# LCD_big.net
KiCad netlist of a schematic drawn in Altium Designer
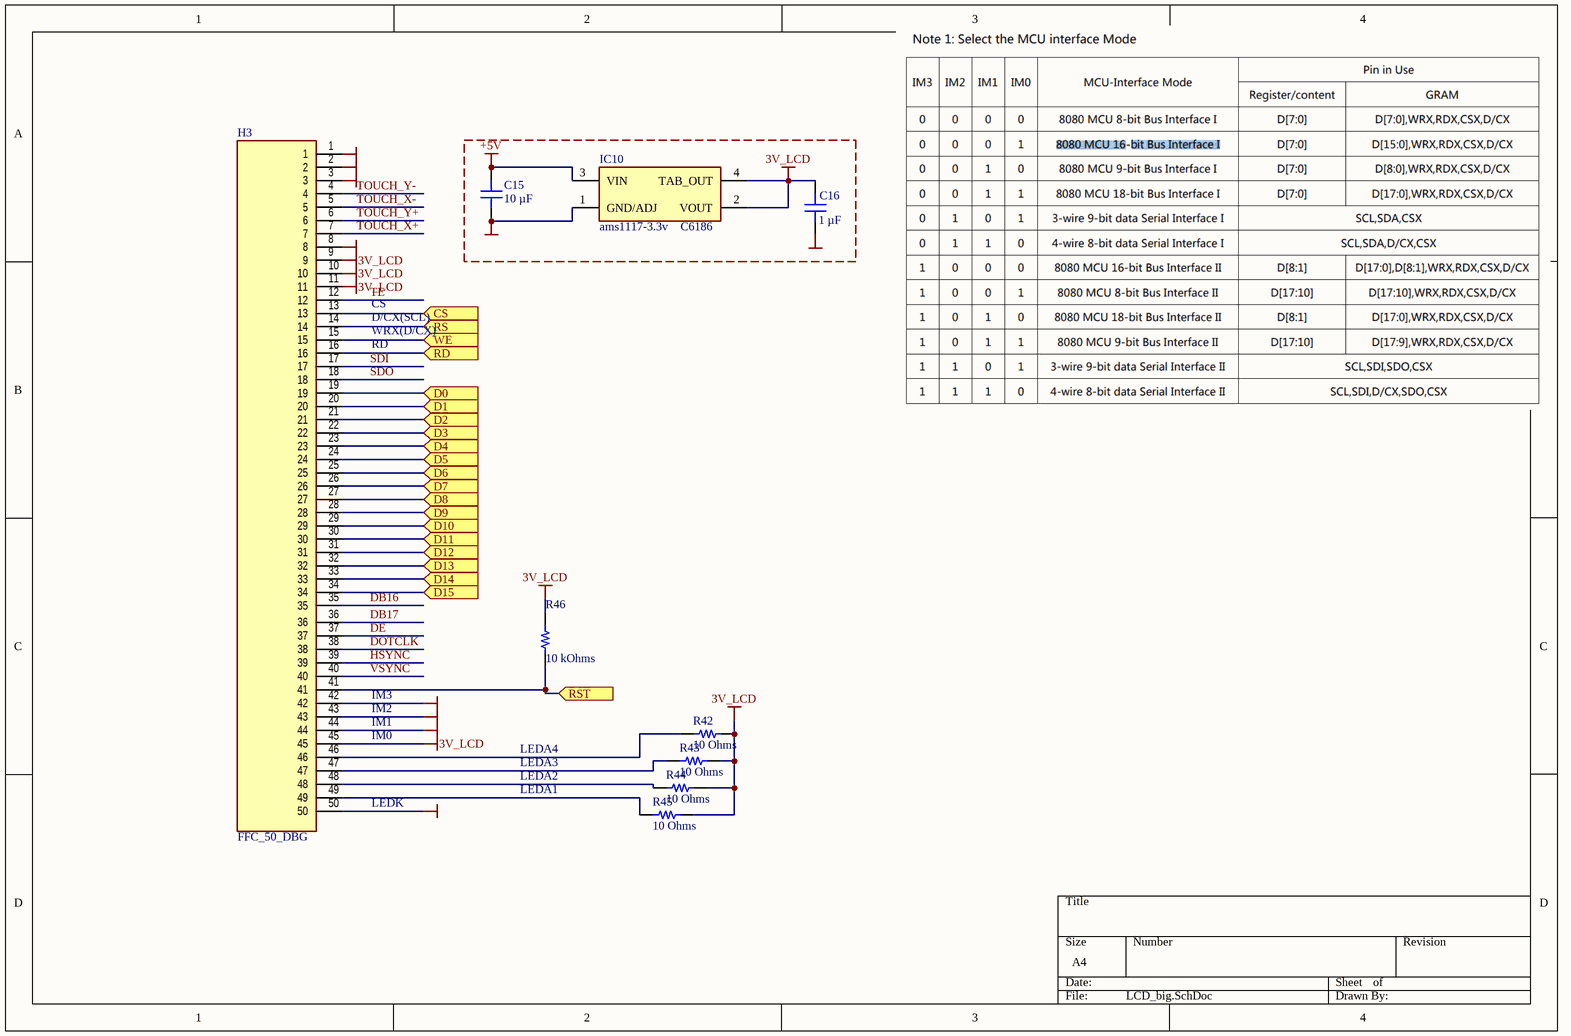
[diagram p0: LCD_big.SchDoc]

(export (version "E")
  (design (tool "Eeschema 10.0.6"))
  (components
    (comp (ref "C15")
      (value "10 µF")
      (footprint "CAP 0805_2012")
      (description "CAP CER 10UF 10V X5R 0805")
      (fields (field (name "PART NUMBER") "C0805C106K8PAC7800") (field (name "MANUFACTURER") "KEMET"))
      (libsource (lib "Celestial Altium Library - altium_library") (part "Capacitor"))
    )
    (comp (ref "C16")
      (value "1 µF")
      (footprint "CAP 0805_2012")
      (description "CAP CER 1UF 16V X7R 0805")
      (fields (field (name "PART NUMBER") "C0805C105K4RAC7800") (field (name "MANUFACTURER") "KEMET"))
      (libsource (lib "Celestial Altium Library - altium_library") (part "Capacitor"))
    )
    (comp (ref "H3")
      (value "FFC_50_DBG")
      (footprint "ProtoStack_H750VBT:FFC_50_DBG")
      (libsource (lib "ProtoStack_H750VBT") (part "FFC_50_DBG"))
    )
    (comp (ref "IC10")
      (value "ams1117-3.3v")
      (footprint "ProtoStack_H750VBT:SOT-223")
      (description "Integrated Circuit")
      (fields (field (name "SUPPLIER PART NUMBER 1") "C6186"))
      (libsource (lib "ProtoStack_H750VBT") (part "ams1117-3.3v"))
    )
    (comp (ref "R42")
      (value "10 Ohms")
      (footprint "RES 0603_1608")
      (description "RES SMD 10 OHM 1% 1/3W 0603")
      (fields
        (field (name "PART NUMBER") "ERJ-PA3F10R0V")
        (field (name "MANUFACTURER") "Panasonic Electronic Components")
      )
      (libsource (lib "Celestial Altium Library - altium_library") (part "Resistor"))
    )
    (comp (ref "R43")
      (value "10 Ohms")
      (footprint "RES 0603_1608")
      (description "RES SMD 10 OHM 1% 1/3W 0603")
      (fields
        (field (name "PART NUMBER") "ERJ-PA3F10R0V")
        (field (name "MANUFACTURER") "Panasonic Electronic Components")
      )
      (libsource (lib "Celestial Altium Library - altium_library") (part "Resistor"))
    )
    (comp (ref "R44")
      (value "10 Ohms")
      (footprint "RES 0603_1608")
      (description "RES SMD 10 OHM 1% 1/3W 0603")
      (fields
        (field (name "PART NUMBER") "ERJ-PA3F10R0V")
        (field (name "MANUFACTURER") "Panasonic Electronic Components")
      )
      (libsource (lib "Celestial Altium Library - altium_library") (part "Resistor"))
    )
    (comp (ref "R45")
      (value "10 Ohms")
      (footprint "RES 0603_1608")
      (description "RES SMD 10 OHM 1% 1/3W 0603")
      (fields
        (field (name "PART NUMBER") "ERJ-PA3F10R0V")
        (field (name "MANUFACTURER") "Panasonic Electronic Components")
      )
      (libsource (lib "Celestial Altium Library - altium_library") (part "Resistor"))
    )
    (comp (ref "R46")
      (value "10 kOhms")
      (footprint "RES 0603_1608")
      (description "RES SMD 10K OHM 1% 1/10W 0603")
      (fields (field (name "PART NUMBER") "RT0603FRE0710KL") (field (name "MANUFACTURER") "Yageo"))
      (libsource (lib "Celestial Altium Library - altium_library") (part "Resistor"))
    )
  )
  (nets
    (net (code "1") (name "+5V") (class "Default")
      (node (ref "C15") (pin "2") (pinfunction "2_2") (pintype "passive"))
      (node (ref "IC10") (pin "3") (pinfunction "VIN_3") (pintype "passive"))
    )
    (net (code "2") (name "/CS") (class "Default")
      (node (ref "H3") (pin "13") (pinfunction "13_13") (pintype "passive"))
    )
    (net (code "3") (name "/D0") (class "Default")
      (node (ref "H3") (pin "19") (pinfunction "19_19") (pintype "passive"))
    )
    (net (code "4") (name "/D1") (class "Default")
      (node (ref "H3") (pin "20") (pinfunction "20_20") (pintype "passive"))
    )
    (net (code "5") (name "/D2") (class "Default")
      (node (ref "H3") (pin "21") (pinfunction "21_21") (pintype "passive"))
    )
    (net (code "6") (name "/D3") (class "Default")
      (node (ref "H3") (pin "22") (pinfunction "22_22") (pintype "passive"))
    )
    (net (code "7") (name "/D4") (class "Default")
      (node (ref "H3") (pin "23") (pinfunction "23_23") (pintype "passive"))
    )
    (net (code "8") (name "/D5") (class "Default")
      (node (ref "H3") (pin "24") (pinfunction "24_24") (pintype "passive"))
    )
    (net (code "9") (name "/D6") (class "Default")
      (node (ref "H3") (pin "25") (pinfunction "25_25") (pintype "passive"))
    )
    (net (code "10") (name "/D7") (class "Default")
      (node (ref "H3") (pin "26") (pinfunction "26_26") (pintype "passive"))
    )
    (net (code "11") (name "/D8") (class "Default")
      (node (ref "H3") (pin "27") (pinfunction "27_27") (pintype "passive"))
    )
    (net (code "12") (name "/D9") (class "Default")
      (node (ref "H3") (pin "28") (pinfunction "28_28") (pintype "passive"))
    )
    (net (code "13") (name "/D10") (class "Default")
      (node (ref "H3") (pin "29") (pinfunction "29_29") (pintype "passive"))
    )
    (net (code "14") (name "/D11") (class "Default")
      (node (ref "H3") (pin "30") (pinfunction "30_30") (pintype "passive"))
    )
    (net (code "15") (name "/D12") (class "Default")
      (node (ref "H3") (pin "31") (pinfunction "31_31") (pintype "passive"))
    )
    (net (code "16") (name "/D13") (class "Default")
      (node (ref "H3") (pin "32") (pinfunction "32_32") (pintype "passive"))
    )
    (net (code "17") (name "/D14") (class "Default")
      (node (ref "H3") (pin "33") (pinfunction "33_33") (pintype "passive"))
    )
    (net (code "18") (name "/D15") (class "Default")
      (node (ref "H3") (pin "34") (pinfunction "34_34") (pintype "passive"))
    )
    (net (code "19") (name "/DB16") (class "Default")
      (node (ref "H3") (pin "35") (pinfunction "35_35") (pintype "passive"))
    )
    (net (code "20") (name "/DB17") (class "Default")
      (node (ref "H3") (pin "36") (pinfunction "36_36") (pintype "passive"))
    )
    (net (code "21") (name "/DE") (class "Default")
      (node (ref "H3") (pin "37") (pinfunction "37_37") (pintype "passive"))
    )
    (net (code "22") (name "/DOTCLK") (class "Default")
      (node (ref "H3") (pin "38") (pinfunction "38_38") (pintype "passive"))
    )
    (net (code "23") (name "/HSYNC") (class "Default")
      (node (ref "H3") (pin "39") (pinfunction "39_39") (pintype "passive"))
    )
    (net (code "24") (name "/RD") (class "Default")
      (node (ref "H3") (pin "16") (pinfunction "16_16") (pintype "passive"))
    )
    (net (code "25") (name "/RS") (class "Default")
      (node (ref "H3") (pin "14") (pinfunction "14_14") (pintype "passive"))
    )
    (net (code "26") (name "/RST") (class "Default")
      (node (ref "H3") (pin "41") (pinfunction "41_41") (pintype "passive"))
      (node (ref "R46") (pin "1") (pinfunction "1_1") (pintype "passive"))
    )
    (net (code "27") (name "/SDI") (class "Default")
      (node (ref "H3") (pin "17") (pinfunction "17_17") (pintype "passive"))
    )
    (net (code "28") (name "/SDO") (class "Default")
      (node (ref "H3") (pin "18") (pinfunction "18_18") (pintype "passive"))
    )
    (net (code "29") (name "/TE") (class "Default")
      (node (ref "H3") (pin "12") (pinfunction "12_12") (pintype "passive"))
    )
    (net (code "30") (name "/TOUCH_X+") (class "Default")
      (node (ref "H3") (pin "7") (pinfunction "7_7") (pintype "passive"))
    )
    (net (code "31") (name "/TOUCH_X-") (class "Default")
      (node (ref "H3") (pin "5") (pinfunction "5_5") (pintype "passive"))
    )
    (net (code "32") (name "/TOUCH_Y+") (class "Default")
      (node (ref "H3") (pin "6") (pinfunction "6_6") (pintype "passive"))
    )
    (net (code "33") (name "/TOUCH_Y-") (class "Default")
      (node (ref "H3") (pin "4") (pinfunction "4_4") (pintype "passive"))
    )
    (net (code "34") (name "/VSYNC") (class "Default")
      (node (ref "H3") (pin "40") (pinfunction "40_40") (pintype "passive"))
    )
    (net (code "35") (name "/WE") (class "Default")
      (node (ref "H3") (pin "15") (pinfunction "15_15") (pintype "passive"))
    )
    (net (code "36") (name "3V_LCD") (class "Default")
      (node (ref "C16") (pin "2") (pinfunction "2_2") (pintype "passive"))
      (node (ref "H3") (pin "10") (pinfunction "10_10") (pintype "passive"))
      (node (ref "H3") (pin "11") (pinfunction "11_11") (pintype "passive"))
      (node (ref "H3") (pin "45") (pinfunction "45_45") (pintype "passive"))
      (node (ref "H3") (pin "9") (pinfunction "9_9") (pintype "passive"))
      (node (ref "IC10") (pin "2") (pinfunction "VOUT_2") (pintype "passive"))
      (node (ref "IC10") (pin "4") (pinfunction "TAB_OUT_4") (pintype "passive"))
      (node (ref "R42") (pin "2") (pinfunction "2_2") (pintype "passive"))
      (node (ref "R43") (pin "2") (pinfunction "2_2") (pintype "passive"))
      (node (ref "R44") (pin "2") (pinfunction "2_2") (pintype "passive"))
      (node (ref "R45") (pin "2") (pinfunction "2_2") (pintype "passive"))
      (node (ref "R46") (pin "2") (pinfunction "2_2") (pintype "passive"))
    )
    (net (code "37") (name "GND") (class "Default")
      (node (ref "C15") (pin "1") (pinfunction "1_1") (pintype "passive"))
      (node (ref "C16") (pin "1") (pinfunction "1_1") (pintype "passive"))
      (node (ref "H3") (pin "1") (pinfunction "1_1") (pintype "passive"))
      (node (ref "H3") (pin "2") (pinfunction "2_2") (pintype "passive"))
      (node (ref "H3") (pin "3") (pinfunction "3_3") (pintype "passive"))
      (node (ref "H3") (pin "42") (pinfunction "42_42") (pintype "passive"))
      (node (ref "H3") (pin "43") (pinfunction "43_43") (pintype "passive"))
      (node (ref "H3") (pin "44") (pinfunction "44_44") (pintype "passive"))
      (node (ref "H3") (pin "50") (pinfunction "50_50") (pintype "passive"))
      (node (ref "H3") (pin "8") (pinfunction "8_8") (pintype "passive"))
      (node (ref "IC10") (pin "1") (pinfunction "GND/ADJ_1") (pintype "passive"))
    )
    (net (code "38") (name "Net-(H3-Pad46)") (class "Default")
      (node (ref "H3") (pin "46") (pinfunction "46_46") (pintype "passive"))
      (node (ref "R42") (pin "1") (pinfunction "1_1") (pintype "passive"))
    )
    (net (code "39") (name "Net-(H3-Pad47)") (class "Default")
      (node (ref "H3") (pin "47") (pinfunction "47_47") (pintype "passive"))
      (node (ref "R43") (pin "1") (pinfunction "1_1") (pintype "passive"))
    )
    (net (code "40") (name "Net-(H3-Pad48)") (class "Default")
      (node (ref "H3") (pin "48") (pinfunction "48_48") (pintype "passive"))
      (node (ref "R44") (pin "1") (pinfunction "1_1") (pintype "passive"))
    )
    (net (code "41") (name "Net-(H3-Pad49)") (class "Default")
      (node (ref "H3") (pin "49") (pinfunction "49_49") (pintype "passive"))
      (node (ref "R45") (pin "1") (pinfunction "1_1") (pintype "passive"))
    )
  )
)
